# tankMotorDriver.net
KiCad netlist of a schematic drawn in EAGLE
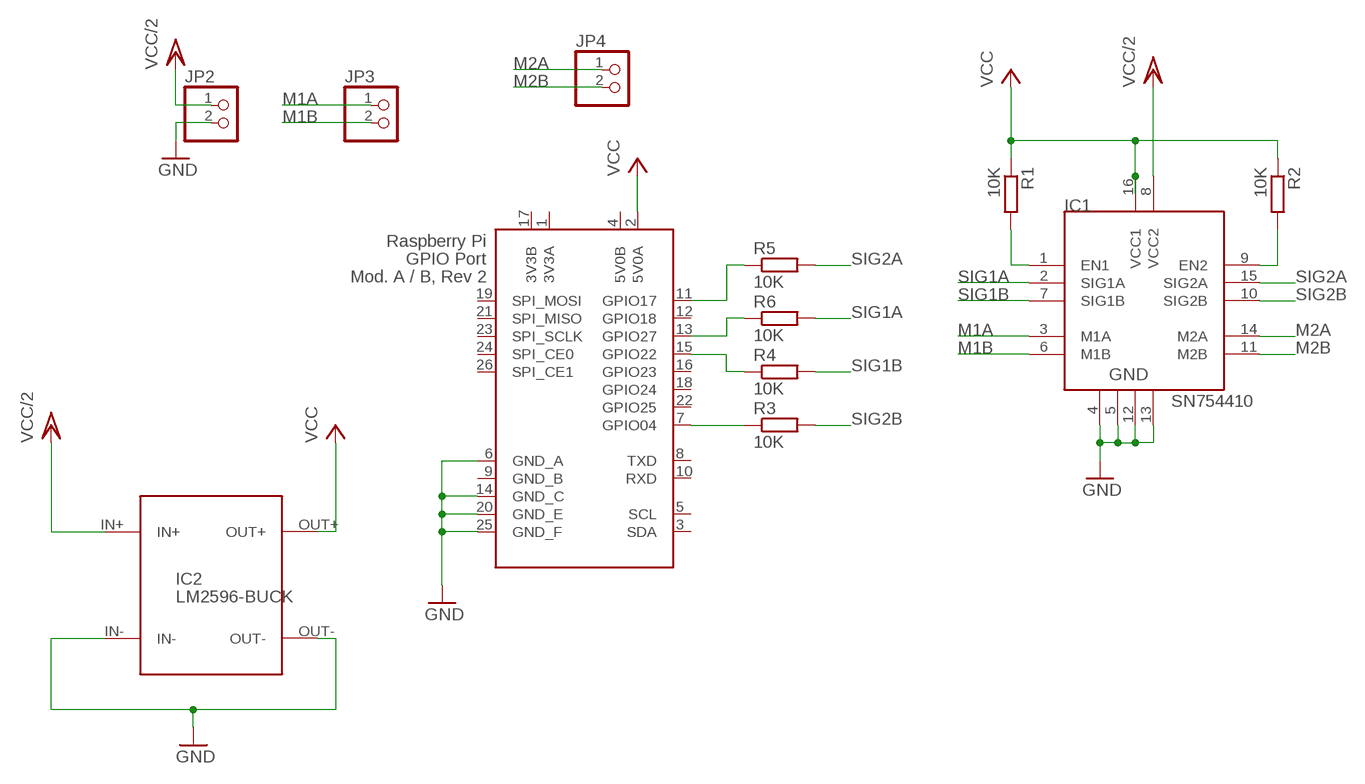
[diagram p0: schematic, sheet 1]

(export (version "E")
  (design (tool "Eeschema 10.0.6"))
  (components
    (comp (ref "IC1")
      (value "SN754410")
      (footprint "eagle-import:DIP16")
      (libsource (lib "eagle-import") (part "SN754410"))
    )
    (comp (ref "IC2")
      (value "LM2596-BUCK")
      (footprint "eagle-import:LM2596-BUCK")
      (libsource (lib "eagle-import") (part "LM2596-BUCK"))
    )
    (comp (ref "JP2")
      (value "PINHD-1X2")
      (footprint "eagle-import:1X02")
      (libsource (lib "eagle-import") (part "PINHD-1X2"))
    )
    (comp (ref "JP3")
      (value "PINHD-1X2")
      (footprint "eagle-import:1X02")
      (libsource (lib "eagle-import") (part "PINHD-1X2"))
    )
    (comp (ref "JP4")
      (value "PINHD-1X2")
      (footprint "eagle-import:1X02")
      (libsource (lib "eagle-import") (part "PINHD-1X2"))
    )
    (comp (ref "R1")
      (value "10K")
      (footprint "eagle-import:0207_10")
      (libsource (lib "eagle-import") (part "R-EU_0207/10"))
    )
    (comp (ref "R2")
      (value "10K")
      (footprint "eagle-import:0207_10")
      (libsource (lib "eagle-import") (part "R-EU_0207/10"))
    )
    (comp (ref "R3")
      (value "10K")
      (footprint "eagle-import:0207_10")
      (libsource (lib "eagle-import") (part "R-EU_0207/10"))
    )
    (comp (ref "R4")
      (value "10K")
      (footprint "eagle-import:0207_10")
      (libsource (lib "eagle-import") (part "R-EU_0207/10"))
    )
    (comp (ref "R5")
      (value "10K")
      (footprint "eagle-import:0207_10")
      (libsource (lib "eagle-import") (part "R-EU_0207/10"))
    )
    (comp (ref "R6")
      (value "10K")
      (footprint "eagle-import:0207_10")
      (libsource (lib "eagle-import") (part "R-EU_0207/10"))
    )
    (comp (ref "X1")
      (value "RASPI_GPIO_AB#_PIN")
      (footprint "eagle-import:RASPI_GPIO_AB_PIN")
      (libsource (lib "eagle-import") (part "RASPI_GPIO_AB#_PIN"))
    )
  )
  (nets
    (net (code "1") (name "/3V3A") (class "Default")
      (node (ref "X1") (pin "1") (pinfunction "3V3A_1") (pintype "power_in"))
    )
    (net (code "2") (name "/3V3B") (class "Default")
      (node (ref "X1") (pin "17") (pinfunction "3V3B_17") (pintype "power_in"))
    )
    (net (code "3") (name "/5V0B") (class "Default")
      (node (ref "X1") (pin "4") (pinfunction "5V0B_4") (pintype "power_in"))
    )
    (net (code "4") (name "/GND_B") (class "Default")
      (node (ref "X1") (pin "9") (pinfunction "GND_B_9") (pintype "power_in"))
    )
    (net (code "5") (name "/M1A") (class "Default")
      (node (ref "IC1") (pin "3") (pinfunction "M1A_3") (pintype "bidirectional"))
      (node (ref "JP3") (pin "1") (pinfunction "1_1") (pintype "passive"))
    )
    (net (code "6") (name "/M1B") (class "Default")
      (node (ref "IC1") (pin "6") (pinfunction "M1B_6") (pintype "bidirectional"))
      (node (ref "JP3") (pin "2") (pinfunction "2_2") (pintype "passive"))
    )
    (net (code "7") (name "/M2A") (class "Default")
      (node (ref "IC1") (pin "14") (pinfunction "M2A_14") (pintype "bidirectional"))
      (node (ref "JP4") (pin "1") (pinfunction "1_1") (pintype "passive"))
    )
    (net (code "8") (name "/M2B") (class "Default")
      (node (ref "IC1") (pin "11") (pinfunction "M2B_11") (pintype "bidirectional"))
      (node (ref "JP4") (pin "2") (pinfunction "2_2") (pintype "passive"))
    )
    (net (code "9") (name "/SIG1A") (class "Default")
      (node (ref "IC1") (pin "2") (pinfunction "SIG1A_2") (pintype "bidirectional"))
      (node (ref "R6") (pin "2") (pinfunction "2_2") (pintype "passive"))
    )
    (net (code "10") (name "/SIG1B") (class "Default")
      (node (ref "IC1") (pin "7") (pinfunction "SIG1B_7") (pintype "bidirectional"))
      (node (ref "R4") (pin "2") (pinfunction "2_2") (pintype "passive"))
    )
    (net (code "11") (name "/SIG2A") (class "Default")
      (node (ref "IC1") (pin "15") (pinfunction "SIG2A_15") (pintype "bidirectional"))
      (node (ref "R5") (pin "2") (pinfunction "2_2") (pintype "passive"))
    )
    (net (code "12") (name "/SIG2B") (class "Default")
      (node (ref "IC1") (pin "10") (pinfunction "SIG2B_10") (pintype "bidirectional"))
      (node (ref "R3") (pin "2") (pinfunction "2_2") (pintype "passive"))
    )
    (net (code "13") (name "GND") (class "Default")
      (node (ref "IC1") (pin "12") (pinfunction "P12_12") (pintype "power_in"))
      (node (ref "IC1") (pin "13") (pinfunction "P13_13") (pintype "power_in"))
      (node (ref "IC1") (pin "4") (pinfunction "P4_4") (pintype "power_in"))
      (node (ref "IC1") (pin "5") (pinfunction "P5_5") (pintype "power_in"))
      (node (ref "IC2") (pin "IN-") (pinfunction "IN-_IN-") (pintype "input"))
      (node (ref "IC2") (pin "OUT-") (pinfunction "OUT-_OUT-") (pintype "output"))
      (node (ref "JP2") (pin "2") (pinfunction "2_2") (pintype "passive"))
      (node (ref "X1") (pin "14") (pinfunction "GND_C_14") (pintype "power_in"))
      (node (ref "X1") (pin "20") (pinfunction "GND_E_20") (pintype "power_in"))
      (node (ref "X1") (pin "25") (pinfunction "GND_F_25") (pintype "power_in"))
      (node (ref "X1") (pin "6") (pinfunction "GND_A_6") (pintype "power_in"))
    )
    (net (code "14") (name "Net-(IC1-EN1)") (class "Default")
      (node (ref "IC1") (pin "1") (pinfunction "EN1_1") (pintype "bidirectional"))
      (node (ref "R1") (pin "2") (pinfunction "2_2") (pintype "passive"))
    )
    (net (code "15") (name "Net-(IC1-EN2)") (class "Default")
      (node (ref "IC1") (pin "9") (pinfunction "EN2_9") (pintype "bidirectional"))
      (node (ref "R2") (pin "2") (pinfunction "2_2") (pintype "passive"))
    )
    (net (code "16") (name "Net-(X1-GPIO04)") (class "Default")
      (node (ref "R3") (pin "1") (pinfunction "1_1") (pintype "passive"))
      (node (ref "X1") (pin "7") (pinfunction "GPIO04_7") (pintype "bidirectional"))
    )
    (net (code "17") (name "Net-(X1-GPIO17)") (class "Default")
      (node (ref "R5") (pin "1") (pinfunction "1_1") (pintype "passive"))
      (node (ref "X1") (pin "11") (pinfunction "GPIO17_11") (pintype "bidirectional"))
    )
    (net (code "18") (name "Net-(X1-GPIO22)") (class "Default")
      (node (ref "R4") (pin "1") (pinfunction "1_1") (pintype "passive"))
      (node (ref "X1") (pin "15") (pinfunction "GPIO22_15") (pintype "bidirectional"))
    )
    (net (code "19") (name "Net-(X1-GPIO27)") (class "Default")
      (node (ref "R6") (pin "1") (pinfunction "1_1") (pintype "passive"))
      (node (ref "X1") (pin "13") (pinfunction "GPIO27_13") (pintype "bidirectional"))
    )
    (net (code "20") (name "VCC") (class "Default")
      (node (ref "IC1") (pin "16") (pinfunction "VCC1_16") (pintype "power_in"))
      (node (ref "IC2") (pin "OUT+") (pinfunction "OUT+_OUT+") (pintype "output"))
      (node (ref "R1") (pin "1") (pinfunction "1_1") (pintype "passive"))
      (node (ref "R2") (pin "1") (pinfunction "1_1") (pintype "passive"))
      (node (ref "X1") (pin "2") (pinfunction "5V0A_2") (pintype "power_in"))
    )
    (net (code "21") (name "VCC{slash}2") (class "Default")
      (node (ref "IC1") (pin "8") (pinfunction "VCC2_8") (pintype "power_in"))
      (node (ref "IC2") (pin "IN+") (pinfunction "IN+_IN+") (pintype "input"))
      (node (ref "JP2") (pin "1") (pinfunction "1_1") (pintype "passive"))
    )
    (net (code "22") (name "unconnected-(X1-GPIO18-Pad12)") (class "Default")
      (node (ref "X1") (pin "12") (pinfunction "GPIO18_12") (pintype "bidirectional"))
    )
    (net (code "23") (name "unconnected-(X1-GPIO23-Pad16)") (class "Default")
      (node (ref "X1") (pin "16") (pinfunction "GPIO23_16") (pintype "bidirectional"))
    )
    (net (code "24") (name "unconnected-(X1-GPIO24-Pad18)") (class "Default")
      (node (ref "X1") (pin "18") (pinfunction "GPIO24_18") (pintype "bidirectional"))
    )
    (net (code "25") (name "unconnected-(X1-GPIO25-Pad22)") (class "Default")
      (node (ref "X1") (pin "22") (pinfunction "GPIO25_22") (pintype "bidirectional"))
    )
    (net (code "26") (name "unconnected-(X1-RXD-Pad10)") (class "Default")
      (node (ref "X1") (pin "10") (pinfunction "RXD_10") (pintype "bidirectional"))
    )
    (net (code "27") (name "unconnected-(X1-SCL-Pad5)") (class "Default")
      (node (ref "X1") (pin "5") (pinfunction "SCL_5") (pintype "bidirectional"))
    )
    (net (code "28") (name "unconnected-(X1-SDA-Pad3)") (class "Default")
      (node (ref "X1") (pin "3") (pinfunction "SDA_3") (pintype "bidirectional"))
    )
    (net (code "29") (name "unconnected-(X1-SPI_CE0-Pad24)") (class "Default")
      (node (ref "X1") (pin "24") (pinfunction "SPI_CE0_24") (pintype "bidirectional"))
    )
    (net (code "30") (name "unconnected-(X1-SPI_CE1-Pad26)") (class "Default")
      (node (ref "X1") (pin "26") (pinfunction "SPI_CE1_26") (pintype "bidirectional"))
    )
    (net (code "31") (name "unconnected-(X1-SPI_MISO-Pad21)") (class "Default")
      (node (ref "X1") (pin "21") (pinfunction "SPI_MISO_21") (pintype "bidirectional"))
    )
    (net (code "32") (name "unconnected-(X1-SPI_MOSI-Pad19)") (class "Default")
      (node (ref "X1") (pin "19") (pinfunction "SPI_MOSI_19") (pintype "bidirectional"))
    )
    (net (code "33") (name "unconnected-(X1-SPI_SCLK-Pad23)") (class "Default")
      (node (ref "X1") (pin "23") (pinfunction "SPI_SCLK_23") (pintype "bidirectional"))
    )
    (net (code "34") (name "unconnected-(X1-TXD-Pad8)") (class "Default")
      (node (ref "X1") (pin "8") (pinfunction "TXD_8") (pintype "bidirectional"))
    )
  )
)
